# CW340_FTDI_LevelShifting.net
KiCad netlist of a schematic drawn in Altium Designer
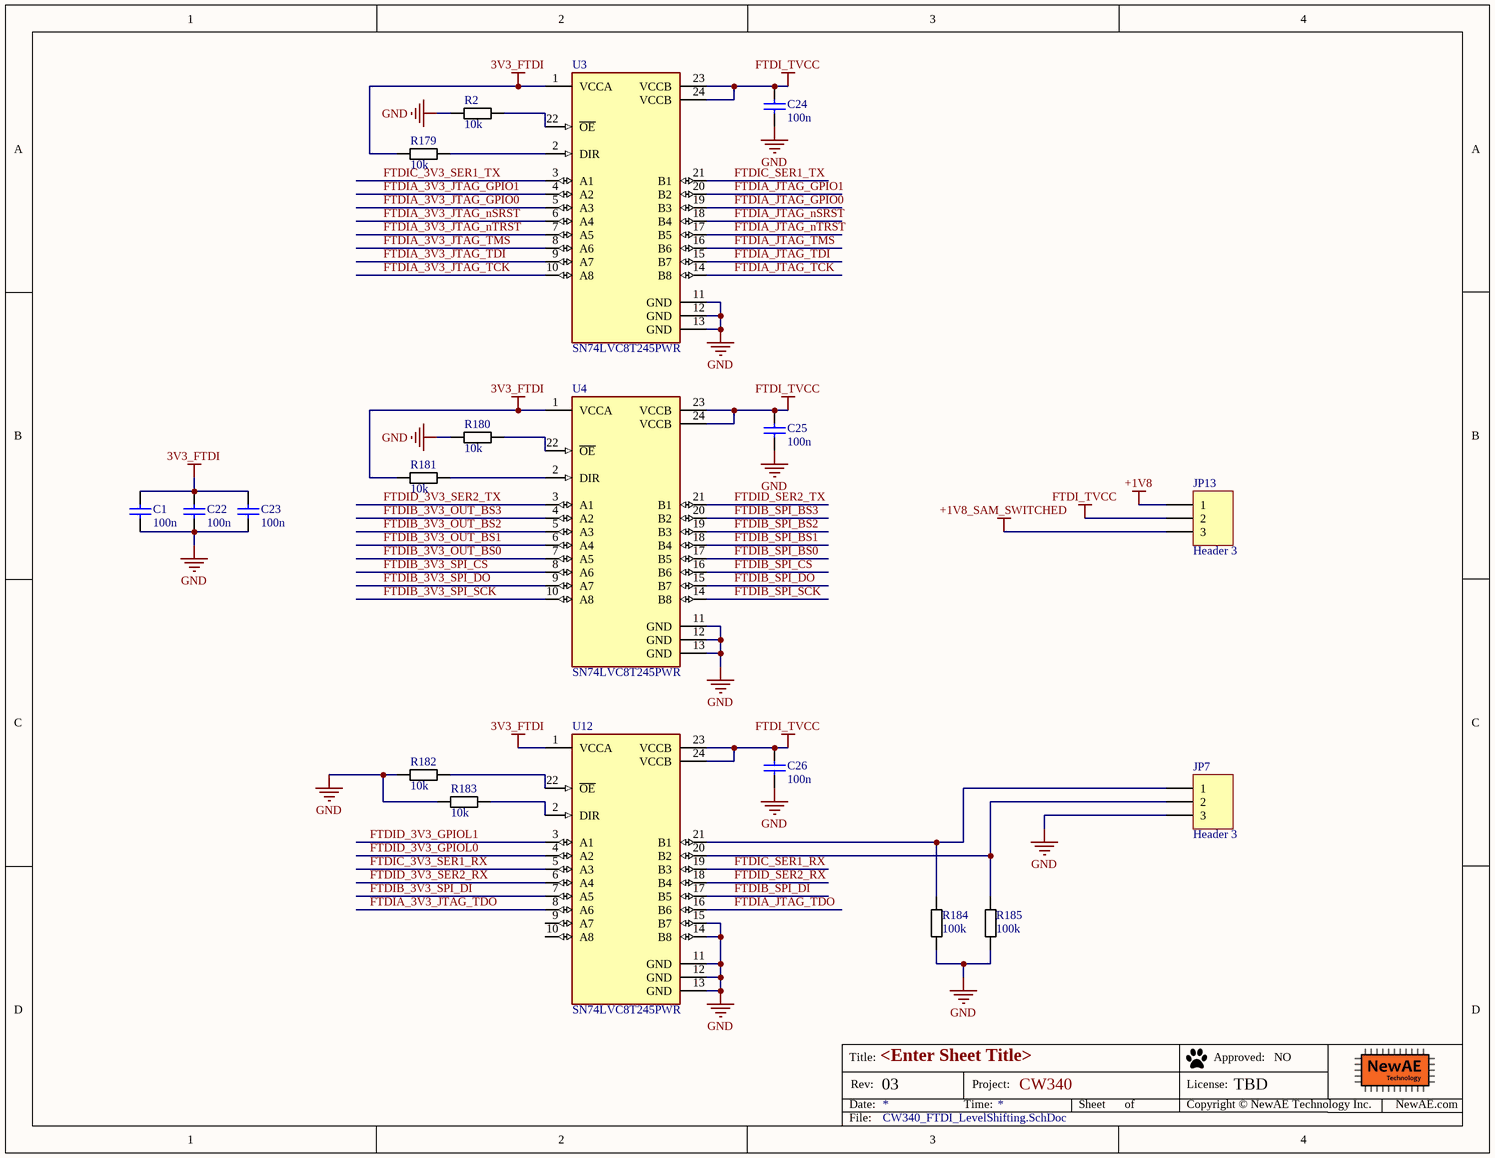
[diagram p0: CW340_FTDI_LevelShifting.SchDoc]

(export (version "E")
  (design (tool "Eeschema 10.0.6"))
  (components
    (comp (ref "C1")
      (value "100n")
      (footprint "CAPC0402_M")
      (description "100n, 0402")
      (fields (field (name "PART NUMBER") "CCHIP-100n-0402"))
      (libsource (lib "NewAE_AltiumLib") (part "CAP"))
    )
    (comp (ref "C22")
      (value "100n")
      (footprint "CAPC0402_M")
      (description "100n, 0402")
      (fields (field (name "PART NUMBER") "CCHIP-100n-0402"))
      (libsource (lib "NewAE_AltiumLib") (part "CAP"))
    )
    (comp (ref "C23")
      (value "100n")
      (footprint "CAPC0402_M")
      (description "100n, 0402")
      (fields (field (name "PART NUMBER") "CCHIP-100n-0402"))
      (libsource (lib "NewAE_AltiumLib") (part "CAP"))
    )
    (comp (ref "C24")
      (value "100n")
      (footprint "CAPC0402_M")
      (description "100n, 0402")
      (fields (field (name "PART NUMBER") "CCHIP-100n-0402"))
      (libsource (lib "NewAE_AltiumLib") (part "CAP"))
    )
    (comp (ref "C25")
      (value "100n")
      (footprint "CAPC0402_M")
      (description "100n, 0402")
      (fields (field (name "PART NUMBER") "CCHIP-100n-0402"))
      (libsource (lib "NewAE_AltiumLib") (part "CAP"))
    )
    (comp (ref "C26")
      (value "100n")
      (footprint "CAPC0402_M")
      (description "100n, 0402")
      (fields (field (name "PART NUMBER") "CCHIP-100n-0402"))
      (libsource (lib "NewAE_AltiumLib") (part "CAP"))
    )
    (comp (ref "JP7")
      (value "Header 3")
      (footprint "HDR1X3")
      (description "Header, 3-Pin")
      (fields (field (name "PUBLISHER") "Altium Limited"))
      (libsource (lib "Miscellaneous Connectors") (part "Header 3"))
    )
    (comp (ref "JP13")
      (value "Header 3")
      (footprint "HDR1X3")
      (description "Header, 3-Pin")
      (fields (field (name "PUBLISHER") "Altium Limited"))
      (libsource (lib "Miscellaneous Connectors") (part "Header 3"))
    )
    (comp (ref "R2")
      (value "10k")
      (footprint "RESC1005X40N")
      (description "10k res, 0402, 1%, 1/16W")
      (fields (field (name "PART NUMBER") "RCHIP-10K-0402") (field (name "TOLERANCE") "1%"))
      (libsource (lib "NewAE_AltiumLib") (part "RES-EU"))
    )
    (comp (ref "R179")
      (value "10k")
      (footprint "RESC1005X40N")
      (description "10k res, 0402, 1%, 1/16W")
      (fields (field (name "PART NUMBER") "RCHIP-10K-0402") (field (name "TOLERANCE") "1%"))
      (libsource (lib "NewAE_AltiumLib") (part "RES-EU"))
    )
    (comp (ref "R180")
      (value "10k")
      (footprint "RESC1005X40N")
      (description "10k res, 0402, 1%, 1/16W")
      (fields (field (name "PART NUMBER") "RCHIP-10K-0402") (field (name "TOLERANCE") "1%"))
      (libsource (lib "NewAE_AltiumLib") (part "RES-EU"))
    )
    (comp (ref "R181")
      (value "10k")
      (footprint "RESC1005X40N")
      (description "10k res, 0402, 1%, 1/16W")
      (fields (field (name "PART NUMBER") "RCHIP-10K-0402") (field (name "TOLERANCE") "1%"))
      (libsource (lib "NewAE_AltiumLib") (part "RES-EU"))
    )
    (comp (ref "R182")
      (value "10k")
      (footprint "RESC1005X40N")
      (description "10k res, 0402, 1%, 1/16W")
      (fields (field (name "PART NUMBER") "RCHIP-10K-0402") (field (name "TOLERANCE") "1%"))
      (libsource (lib "NewAE_AltiumLib") (part "RES-EU"))
    )
    (comp (ref "R183")
      (value "10k")
      (footprint "RESC1005X40N")
      (description "10k res, 0402, 1%, 1/16W")
      (fields (field (name "PART NUMBER") "RCHIP-10K-0402") (field (name "TOLERANCE") "1%"))
      (libsource (lib "NewAE_AltiumLib") (part "RES-EU"))
    )
    (comp (ref "R184")
      (value "100k")
      (footprint "RESC1608X55N")
      (description "100k res, 0603, 1%, 1/10W")
      (fields (field (name "PART NUMBER") "RCHIP-100K-0603") (field (name "TOLERANCE") "1%"))
      (libsource (lib "") (part "RES-EU_1"))
    )
    (comp (ref "R185")
      (value "100k")
      (footprint "RESC1608X55N")
      (description "100k res, 0603, 1%, 1/10W")
      (fields (field (name "PART NUMBER") "RCHIP-100K-0603") (field (name "TOLERANCE") "1%"))
      (libsource (lib "") (part "RES-EU_1"))
    )
    (comp (ref "U3")
      (value "SN74LVC8T245PWR")
      (footprint "FP-PW0024A-MFG")
      (description "IC TRNSLTR BIDIRECTIONAL 24TSSOP")
      (fields
        (field (name "OCTOPART") "https://octopart.com/sn74lvc8t245pwr-texas+instruments-517164")
        (field (name "MANUFACTURER") "Texas Instruments")
      )
      (libsource (lib "Altium Content Vault") (part "51221a7e4c45eff2cf920f7ccaf63e0"))
    )
    (comp (ref "U4")
      (value "SN74LVC8T245PWR")
      (footprint "FP-PW0024A-MFG")
      (description "IC TRNSLTR BIDIRECTIONAL 24TSSOP")
      (fields
        (field (name "OCTOPART") "https://octopart.com/sn74lvc8t245pwr-texas+instruments-517164")
        (field (name "MANUFACTURER") "Texas Instruments")
      )
      (libsource (lib "Altium Content Vault") (part "51221a7e4c45eff2cf920f7ccaf63e0"))
    )
    (comp (ref "U12")
      (value "SN74LVC8T245PWR")
      (footprint "FP-PW0024A-MFG")
      (description "IC TRNSLTR BIDIRECTIONAL 24TSSOP")
      (fields
        (field (name "OCTOPART") "https://octopart.com/sn74lvc8t245pwr-texas+instruments-517164")
        (field (name "MANUFACTURER") "Texas Instruments")
      )
      (libsource (lib "Altium Content Vault") (part "51221a7e4c45eff2cf920f7ccaf63e0"))
    )
  )
  (nets
    (net (code "1") (name "+1V8") (class "Default")
      (node (ref "JP13") (pin "1") (pinfunction "1_1") (pintype "passive"))
    )
    (net (code "2") (name "+1V8_SAM_SWITCHED") (class "Default")
      (node (ref "JP13") (pin "3") (pinfunction "3_3") (pintype "passive"))
    )
    (net (code "3") (name "/FTDIA_3V3_JTAG_GPIO0") (class "Default")
      (node (ref "U3") (pin "5") (pinfunction "A3_5") (pintype "bidirectional"))
    )
    (net (code "4") (name "/FTDIA_3V3_JTAG_GPIO1") (class "Default")
      (node (ref "U3") (pin "4") (pinfunction "A2_4") (pintype "bidirectional"))
    )
    (net (code "5") (name "/FTDIA_3V3_JTAG_TCK") (class "Default")
      (node (ref "U3") (pin "10") (pinfunction "A8_10") (pintype "bidirectional"))
    )
    (net (code "6") (name "/FTDIA_3V3_JTAG_TDI") (class "Default")
      (node (ref "U3") (pin "9") (pinfunction "A7_9") (pintype "bidirectional"))
    )
    (net (code "7") (name "/FTDIA_3V3_JTAG_TDO") (class "Default")
      (node (ref "U12") (pin "8") (pinfunction "A6_8") (pintype "bidirectional"))
    )
    (net (code "8") (name "/FTDIA_3V3_JTAG_TMS") (class "Default")
      (node (ref "U3") (pin "8") (pinfunction "A6_8") (pintype "bidirectional"))
    )
    (net (code "9") (name "/FTDIA_3V3_JTAG_nSRST") (class "Default")
      (node (ref "U3") (pin "6") (pinfunction "A4_6") (pintype "bidirectional"))
    )
    (net (code "10") (name "/FTDIA_3V3_JTAG_nTRST") (class "Default")
      (node (ref "U3") (pin "7") (pinfunction "A5_7") (pintype "bidirectional"))
    )
    (net (code "11") (name "/FTDIA_JTAG_GPIO0") (class "Default")
      (node (ref "U3") (pin "19") (pinfunction "B3_19") (pintype "bidirectional"))
    )
    (net (code "12") (name "/FTDIA_JTAG_GPIO1") (class "Default")
      (node (ref "U3") (pin "20") (pinfunction "B2_20") (pintype "bidirectional"))
    )
    (net (code "13") (name "/FTDIA_JTAG_TCK") (class "Default")
      (node (ref "U3") (pin "14") (pinfunction "B8_14") (pintype "bidirectional"))
    )
    (net (code "14") (name "/FTDIA_JTAG_TDI") (class "Default")
      (node (ref "U3") (pin "15") (pinfunction "B7_15") (pintype "bidirectional"))
    )
    (net (code "15") (name "/FTDIA_JTAG_TDO") (class "Default")
      (node (ref "U12") (pin "16") (pinfunction "B6_16") (pintype "bidirectional"))
    )
    (net (code "16") (name "/FTDIA_JTAG_TMS") (class "Default")
      (node (ref "U3") (pin "16") (pinfunction "B6_16") (pintype "bidirectional"))
    )
    (net (code "17") (name "/FTDIA_JTAG_nSRST") (class "Default")
      (node (ref "U3") (pin "18") (pinfunction "B4_18") (pintype "bidirectional"))
    )
    (net (code "18") (name "/FTDIA_JTAG_nTRST") (class "Default")
      (node (ref "U3") (pin "17") (pinfunction "B5_17") (pintype "bidirectional"))
    )
    (net (code "19") (name "/FTDIB_3V3_OUT_BS0") (class "Default")
      (node (ref "U4") (pin "7") (pinfunction "A5_7") (pintype "bidirectional"))
    )
    (net (code "20") (name "/FTDIB_3V3_OUT_BS1") (class "Default")
      (node (ref "U4") (pin "6") (pinfunction "A4_6") (pintype "bidirectional"))
    )
    (net (code "21") (name "/FTDIB_3V3_OUT_BS2") (class "Default")
      (node (ref "U4") (pin "5") (pinfunction "A3_5") (pintype "bidirectional"))
    )
    (net (code "22") (name "/FTDIB_3V3_OUT_BS3") (class "Default")
      (node (ref "U4") (pin "4") (pinfunction "A2_4") (pintype "bidirectional"))
    )
    (net (code "23") (name "/FTDIB_3V3_SPI_CS") (class "Default")
      (node (ref "U4") (pin "8") (pinfunction "A6_8") (pintype "bidirectional"))
    )
    (net (code "24") (name "/FTDIB_3V3_SPI_DI") (class "Default")
      (node (ref "U12") (pin "7") (pinfunction "A5_7") (pintype "bidirectional"))
    )
    (net (code "25") (name "/FTDIB_3V3_SPI_DO") (class "Default")
      (node (ref "U4") (pin "9") (pinfunction "A7_9") (pintype "bidirectional"))
    )
    (net (code "26") (name "/FTDIB_3V3_SPI_SCK") (class "Default")
      (node (ref "U4") (pin "10") (pinfunction "A8_10") (pintype "bidirectional"))
    )
    (net (code "27") (name "/FTDIB_SPI_BS0") (class "Default")
      (node (ref "U4") (pin "17") (pinfunction "B5_17") (pintype "bidirectional"))
    )
    (net (code "28") (name "/FTDIB_SPI_BS1") (class "Default")
      (node (ref "U4") (pin "18") (pinfunction "B4_18") (pintype "bidirectional"))
    )
    (net (code "29") (name "/FTDIB_SPI_BS2") (class "Default")
      (node (ref "U4") (pin "19") (pinfunction "B3_19") (pintype "bidirectional"))
    )
    (net (code "30") (name "/FTDIB_SPI_BS3") (class "Default")
      (node (ref "U4") (pin "20") (pinfunction "B2_20") (pintype "bidirectional"))
    )
    (net (code "31") (name "/FTDIB_SPI_CS") (class "Default")
      (node (ref "U4") (pin "16") (pinfunction "B6_16") (pintype "bidirectional"))
    )
    (net (code "32") (name "/FTDIB_SPI_DI") (class "Default")
      (node (ref "U12") (pin "17") (pinfunction "B5_17") (pintype "bidirectional"))
    )
    (net (code "33") (name "/FTDIB_SPI_DO") (class "Default")
      (node (ref "U4") (pin "15") (pinfunction "B7_15") (pintype "bidirectional"))
    )
    (net (code "34") (name "/FTDIB_SPI_SCK") (class "Default")
      (node (ref "U4") (pin "14") (pinfunction "B8_14") (pintype "bidirectional"))
    )
    (net (code "35") (name "/FTDIC_3V3_SER1_RX") (class "Default")
      (node (ref "U12") (pin "5") (pinfunction "A3_5") (pintype "bidirectional"))
    )
    (net (code "36") (name "/FTDIC_3V3_SER1_TX") (class "Default")
      (node (ref "U3") (pin "3") (pinfunction "A1_3") (pintype "bidirectional"))
    )
    (net (code "37") (name "/FTDIC_SER1_RX") (class "Default")
      (node (ref "U12") (pin "19") (pinfunction "B3_19") (pintype "bidirectional"))
    )
    (net (code "38") (name "/FTDIC_SER1_TX") (class "Default")
      (node (ref "U3") (pin "21") (pinfunction "B1_21") (pintype "bidirectional"))
    )
    (net (code "39") (name "/FTDID_3V3_GPIOL0") (class "Default")
      (node (ref "U12") (pin "4") (pinfunction "A2_4") (pintype "bidirectional"))
    )
    (net (code "40") (name "/FTDID_3V3_GPIOL1") (class "Default")
      (node (ref "U12") (pin "3") (pinfunction "A1_3") (pintype "bidirectional"))
    )
    (net (code "41") (name "/FTDID_3V3_SER2_RX") (class "Default")
      (node (ref "U12") (pin "6") (pinfunction "A4_6") (pintype "bidirectional"))
    )
    (net (code "42") (name "/FTDID_3V3_SER2_TX") (class "Default")
      (node (ref "U4") (pin "3") (pinfunction "A1_3") (pintype "bidirectional"))
    )
    (net (code "43") (name "/FTDID_SER2_RX") (class "Default")
      (node (ref "U12") (pin "18") (pinfunction "B4_18") (pintype "bidirectional"))
    )
    (net (code "44") (name "/FTDID_SER2_TX") (class "Default")
      (node (ref "U4") (pin "21") (pinfunction "B1_21") (pintype "bidirectional"))
    )
    (net (code "45") (name "3V3_FTDI") (class "Default")
      (node (ref "C1") (pin "1") (pinfunction "1_1") (pintype "passive"))
      (node (ref "C22") (pin "1") (pinfunction "1_1") (pintype "passive"))
      (node (ref "C23") (pin "1") (pinfunction "1_1") (pintype "passive"))
      (node (ref "R179") (pin "2") (pinfunction "2_2") (pintype "passive"))
      (node (ref "R181") (pin "2") (pinfunction "2_2") (pintype "passive"))
      (node (ref "U12") (pin "1") (pinfunction "VCCA_1") (pintype "power_in"))
      (node (ref "U3") (pin "1") (pinfunction "VCCA_1") (pintype "power_in"))
      (node (ref "U4") (pin "1") (pinfunction "VCCA_1") (pintype "power_in"))
    )
    (net (code "46") (name "FTDI_TVCC") (class "Default")
      (node (ref "C24") (pin "1") (pinfunction "1_1") (pintype "passive"))
      (node (ref "C25") (pin "1") (pinfunction "1_1") (pintype "passive"))
      (node (ref "C26") (pin "1") (pinfunction "1_1") (pintype "passive"))
      (node (ref "JP13") (pin "2") (pinfunction "2_2") (pintype "passive"))
      (node (ref "U12") (pin "23") (pinfunction "VCCB_23") (pintype "power_in"))
      (node (ref "U12") (pin "24") (pinfunction "VCCB_24") (pintype "power_in"))
      (node (ref "U3") (pin "23") (pinfunction "VCCB_23") (pintype "power_in"))
      (node (ref "U3") (pin "24") (pinfunction "VCCB_24") (pintype "power_in"))
      (node (ref "U4") (pin "23") (pinfunction "VCCB_23") (pintype "power_in"))
      (node (ref "U4") (pin "24") (pinfunction "VCCB_24") (pintype "power_in"))
    )
    (net (code "47") (name "GND") (class "Default")
      (node (ref "C1") (pin "2") (pinfunction "2_2") (pintype "passive"))
      (node (ref "C22") (pin "2") (pinfunction "2_2") (pintype "passive"))
      (node (ref "C23") (pin "2") (pinfunction "2_2") (pintype "passive"))
      (node (ref "C24") (pin "2") (pinfunction "2_2") (pintype "passive"))
      (node (ref "C25") (pin "2") (pinfunction "2_2") (pintype "passive"))
      (node (ref "C26") (pin "2") (pinfunction "2_2") (pintype "passive"))
      (node (ref "JP7") (pin "3") (pinfunction "3_3") (pintype "passive"))
      (node (ref "R180") (pin "2") (pinfunction "2_2") (pintype "passive"))
      (node (ref "R182") (pin "2") (pinfunction "2_2") (pintype "passive"))
      (node (ref "R183") (pin "2") (pinfunction "2_2") (pintype "passive"))
      (node (ref "R184") (pin "2") (pinfunction "2_2") (pintype "passive"))
      (node (ref "R185") (pin "2") (pinfunction "2_2") (pintype "passive"))
      (node (ref "R2") (pin "2") (pinfunction "2_2") (pintype "passive"))
      (node (ref "U12") (pin "11") (pinfunction "GND_11") (pintype "power_in"))
      (node (ref "U12") (pin "12") (pinfunction "GND_12") (pintype "power_in"))
      (node (ref "U12") (pin "13") (pinfunction "GND_13") (pintype "power_in"))
      (node (ref "U12") (pin "14") (pinfunction "B8_14") (pintype "bidirectional"))
      (node (ref "U12") (pin "15") (pinfunction "B7_15") (pintype "bidirectional"))
      (node (ref "U3") (pin "11") (pinfunction "GND_11") (pintype "power_in"))
      (node (ref "U3") (pin "12") (pinfunction "GND_12") (pintype "power_in"))
      (node (ref "U3") (pin "13") (pinfunction "GND_13") (pintype "power_in"))
      (node (ref "U4") (pin "11") (pinfunction "GND_11") (pintype "power_in"))
      (node (ref "U4") (pin "12") (pinfunction "GND_12") (pintype "power_in"))
      (node (ref "U4") (pin "13") (pinfunction "GND_13") (pintype "power_in"))
    )
    (net (code "48") (name "Net-(U3-DIR)") (class "Default")
      (node (ref "R179") (pin "1") (pinfunction "1_1") (pintype "passive"))
      (node (ref "U3") (pin "2") (pinfunction "DIR_2") (pintype "input"))
    )
    (net (code "49") (name "Net-(U3-~{OE})") (class "Default")
      (node (ref "R2") (pin "1") (pinfunction "1_1") (pintype "passive"))
      (node (ref "U3") (pin "22") (pinfunction "~{OE}_22") (pintype "input"))
    )
    (net (code "50") (name "Net-(U4-DIR)") (class "Default")
      (node (ref "R181") (pin "1") (pinfunction "1_1") (pintype "passive"))
      (node (ref "U4") (pin "2") (pinfunction "DIR_2") (pintype "input"))
    )
    (net (code "51") (name "Net-(U4-~{OE})") (class "Default")
      (node (ref "R180") (pin "1") (pinfunction "1_1") (pintype "passive"))
      (node (ref "U4") (pin "22") (pinfunction "~{OE}_22") (pintype "input"))
    )
    (net (code "52") (name "Net-(U12-B1)") (class "Default")
      (node (ref "JP7") (pin "1") (pinfunction "1_1") (pintype "passive"))
      (node (ref "R184") (pin "1") (pinfunction "1_1") (pintype "passive"))
      (node (ref "U12") (pin "21") (pinfunction "B1_21") (pintype "bidirectional"))
    )
    (net (code "53") (name "Net-(U12-B2)") (class "Default")
      (node (ref "JP7") (pin "2") (pinfunction "2_2") (pintype "passive"))
      (node (ref "R185") (pin "1") (pinfunction "1_1") (pintype "passive"))
      (node (ref "U12") (pin "20") (pinfunction "B2_20") (pintype "bidirectional"))
    )
    (net (code "54") (name "Net-(U12-DIR)") (class "Default")
      (node (ref "R183") (pin "1") (pinfunction "1_1") (pintype "passive"))
      (node (ref "U12") (pin "2") (pinfunction "DIR_2") (pintype "input"))
    )
    (net (code "55") (name "Net-(U12-~{OE})") (class "Default")
      (node (ref "R182") (pin "1") (pinfunction "1_1") (pintype "passive"))
      (node (ref "U12") (pin "22") (pinfunction "~{OE}_22") (pintype "input"))
    )
    (net (code "56") (name "unconnected-(U12-A7-Pad9)") (class "Default")
      (node (ref "U12") (pin "9") (pinfunction "A7_9") (pintype "bidirectional"))
    )
    (net (code "57") (name "unconnected-(U12-A8-Pad10)") (class "Default")
      (node (ref "U12") (pin "10") (pinfunction "A8_10") (pintype "bidirectional"))
    )
  )
)
